# CHARGE.net
KiCad netlist of a schematic drawn in EAGLE
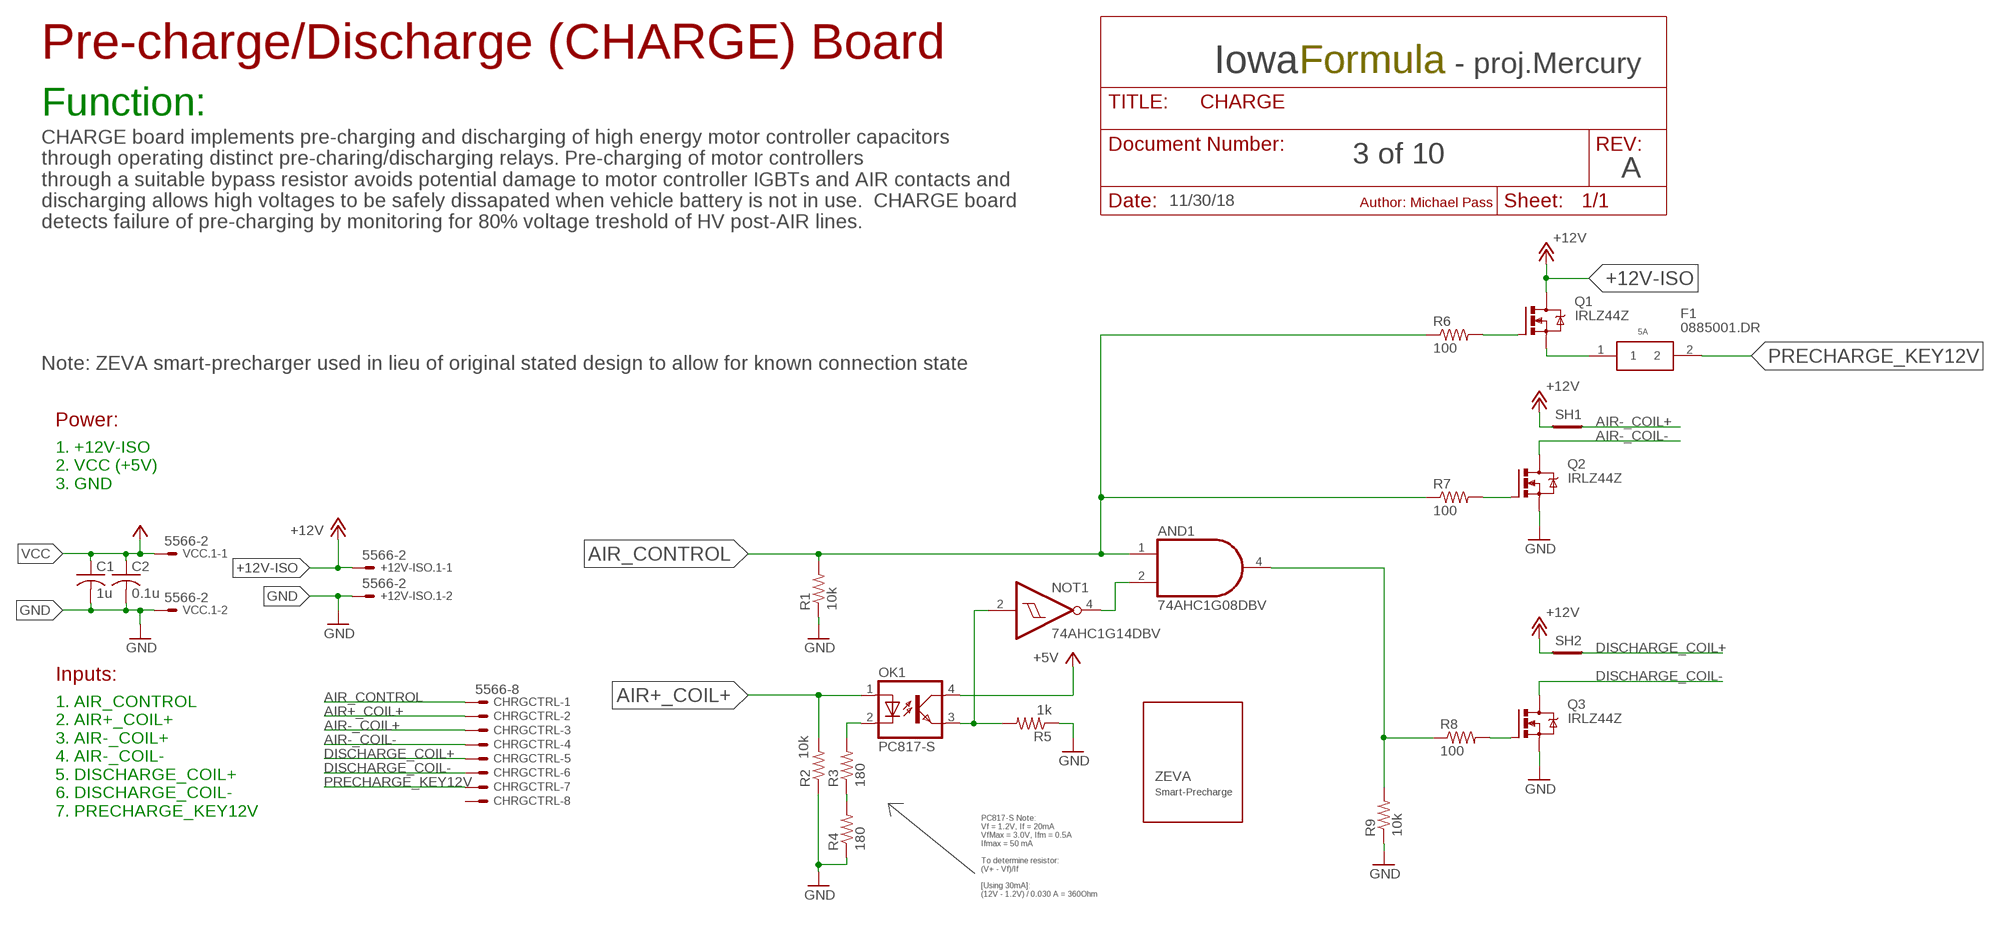
[diagram p0: schematic, sheet 1]

(export (version "E")
  (design (tool "Eeschema 10.0.6"))
  (components
    (comp (ref "+12V-ISO.1")
      (value "5566-2")
      (footprint "eagle-import:5566-2")
      (fields (field (name "MF") "MOLEX"))
      (libsource (lib "eagle-import") (part "5566-2"))
    )
    (comp (ref "AND1")
      (value "74AHC1G08DBV")
      (footprint "eagle-import:SOT23-5")
      (libsource (lib "eagle-import") (part "741G08DBVAHC"))
    )
    (comp (ref "C1")
      (value "1u")
      (footprint "eagle-import:C0805")
      (libsource (lib "eagle-import") (part "C-USC0805"))
    )
    (comp (ref "C2")
      (value "0.1u")
      (footprint "eagle-import:C0805")
      (libsource (lib "eagle-import") (part "C-USC0805"))
    )
    (comp (ref "CHRGCTRL")
      (value "5566-8")
      (footprint "eagle-import:5566-8")
      (fields (field (name "MF") "MOLEX"))
      (libsource (lib "eagle-import") (part "5566-8"))
    )
    (comp (ref "F1")
      (value "0885001.DR")
      (footprint "eagle-import:FUSC10948X488N")
      (fields (field (name "MOUSER_PART_NUMBER") "576-0885001.DR"))
      (libsource (lib "eagle-import") (part "0885001.DR"))
    )
    (comp (ref "NOT1")
      (value "74AHC1G14DBV")
      (footprint "eagle-import:SOT23-5")
      (libsource (lib "eagle-import") (part "741G14DBVAHC"))
    )
    (comp (ref "OK1")
      (value "PC817-S")
      (footprint "eagle-import:SOP04(2.54)")
      (libsource (lib "eagle-import") (part "PC817-S"))
    )
    (comp (ref "Q1")
      (value "IRLZ44Z")
      (footprint "eagle-import:TO220BH")
      (libsource (lib "eagle-import") (part "IRLZ44Z"))
    )
    (comp (ref "Q2")
      (value "IRLZ44Z")
      (footprint "eagle-import:TO220BH")
      (libsource (lib "eagle-import") (part "IRLZ44Z"))
    )
    (comp (ref "Q3")
      (value "IRLZ44Z")
      (footprint "eagle-import:TO220BH")
      (libsource (lib "eagle-import") (part "IRLZ44Z"))
    )
    (comp (ref "R1")
      (value "10k")
      (footprint "eagle-import:R0805")
      (libsource (lib "eagle-import") (part "R-US_R0805"))
    )
    (comp (ref "R2")
      (value "10k")
      (footprint "eagle-import:R0805")
      (libsource (lib "eagle-import") (part "R-US_R0805"))
    )
    (comp (ref "R3")
      (value "180")
      (footprint "eagle-import:R0805")
      (libsource (lib "eagle-import") (part "R-US_R0805"))
    )
    (comp (ref "R4")
      (value "180")
      (footprint "eagle-import:R0805")
      (libsource (lib "eagle-import") (part "R-US_R0805"))
    )
    (comp (ref "R5")
      (value "1k")
      (footprint "eagle-import:R0805")
      (libsource (lib "eagle-import") (part "R-US_R0805"))
    )
    (comp (ref "R6")
      (value "100")
      (footprint "eagle-import:R0805")
      (libsource (lib "eagle-import") (part "R-US_R0805"))
    )
    (comp (ref "R7")
      (value "100")
      (footprint "eagle-import:R0805")
      (libsource (lib "eagle-import") (part "R-US_R0805"))
    )
    (comp (ref "R8")
      (value "100")
      (footprint "eagle-import:R0805")
      (libsource (lib "eagle-import") (part "R-US_R0805"))
    )
    (comp (ref "R9")
      (value "10k")
      (footprint "eagle-import:R0805")
      (libsource (lib "eagle-import") (part "R-US_R0805"))
    )
    (comp (ref "SH1")
      (value "SHORTA5")
      (footprint "eagle-import:SHORT_ALL-50")
      (libsource (lib "eagle-import") (part "SHORTA5"))
    )
    (comp (ref "SH2")
      (value "SHORTA5")
      (footprint "eagle-import:SHORT_ALL-50")
      (libsource (lib "eagle-import") (part "SHORTA5"))
    )
    (comp (ref "U$1")
      (value "ZEVA_SMART-PRECHARGE")
      (footprint "eagle-import:ZEVA")
      (libsource (lib "eagle-import") (part "ZEVA_SMART-PRECHARGE"))
    )
    (comp (ref "VCC.1")
      (value "5566-2")
      (footprint "eagle-import:5566-2")
      (fields (field (name "MF") "MOLEX"))
      (libsource (lib "eagle-import") (part "5566-2"))
    )
  )
  (nets
    (net (code "1") (name "+12V-ISO") (class "Default")
      (node (ref "+12V-ISO.1") (pin "1") (pinfunction "S_1") (pintype "passive"))
      (node (ref "Q1") (pin "D") (pinfunction "D_D") (pintype "passive"))
      (node (ref "SH1") (pin "1") (pinfunction "P$1_1") (pintype "bidirectional"))
      (node (ref "SH2") (pin "1") (pinfunction "P$1_1") (pintype "bidirectional"))
    )
    (net (code "2") (name "/AIR-_COIL+") (class "Default")
      (node (ref "CHRGCTRL") (pin "3") (pinfunction "S_3") (pintype "passive"))
      (node (ref "SH1") (pin "2") (pinfunction "P$2_2") (pintype "bidirectional"))
    )
    (net (code "3") (name "/AIR-_COIL-") (class "Default")
      (node (ref "CHRGCTRL") (pin "4") (pinfunction "S_4") (pintype "passive"))
      (node (ref "Q2") (pin "D") (pinfunction "D_D") (pintype "passive"))
    )
    (net (code "4") (name "/DISCHARGE_COIL+") (class "Default")
      (node (ref "CHRGCTRL") (pin "5") (pinfunction "S_5") (pintype "passive"))
      (node (ref "SH2") (pin "2") (pinfunction "P$2_2") (pintype "bidirectional"))
    )
    (net (code "5") (name "/DISCHARGE_COIL-") (class "Default")
      (node (ref "CHRGCTRL") (pin "6") (pinfunction "S_6") (pintype "passive"))
      (node (ref "Q3") (pin "D") (pinfunction "D_D") (pintype "passive"))
    )
    (net (code "6") (name "AIR+_COIL+") (class "Default")
      (node (ref "CHRGCTRL") (pin "2") (pinfunction "S_2") (pintype "passive"))
      (node (ref "OK1") (pin "1") (pinfunction "A_1") (pintype "passive"))
      (node (ref "R2") (pin "2") (pinfunction "2_2") (pintype "passive"))
    )
    (net (code "7") (name "AIR_CONTROL") (class "Default")
      (node (ref "AND1") (pin "1") (pinfunction "I0_1") (pintype "input"))
      (node (ref "CHRGCTRL") (pin "1") (pinfunction "S_1") (pintype "passive"))
      (node (ref "R1") (pin "2") (pinfunction "2_2") (pintype "passive"))
      (node (ref "R6") (pin "1") (pinfunction "1_1") (pintype "passive"))
      (node (ref "R7") (pin "1") (pinfunction "1_1") (pintype "passive"))
    )
    (net (code "8") (name "GND") (class "Default")
      (node (ref "+12V-ISO.1") (pin "2") (pinfunction "S_2") (pintype "passive"))
      (node (ref "C1") (pin "2") (pinfunction "2_2") (pintype "passive"))
      (node (ref "C2") (pin "2") (pinfunction "2_2") (pintype "passive"))
      (node (ref "Q2") (pin "S") (pinfunction "S_S") (pintype "passive"))
      (node (ref "Q3") (pin "S") (pinfunction "S_S") (pintype "passive"))
      (node (ref "R1") (pin "1") (pinfunction "1_1") (pintype "passive"))
      (node (ref "R2") (pin "1") (pinfunction "1_1") (pintype "passive"))
      (node (ref "R4") (pin "1") (pinfunction "1_1") (pintype "passive"))
      (node (ref "R5") (pin "1") (pinfunction "1_1") (pintype "passive"))
      (node (ref "R9") (pin "1") (pinfunction "1_1") (pintype "passive"))
      (node (ref "VCC.1") (pin "2") (pinfunction "S_2") (pintype "passive"))
    )
    (net (code "9") (name "Net-(AND1A-I1)") (class "Default")
      (node (ref "AND1") (pin "2") (pinfunction "I1_2") (pintype "input"))
      (node (ref "NOT1") (pin "4") (pinfunction "O_4") (pintype "output"))
    )
    (net (code "10") (name "Net-(AND1A-O)") (class "Default")
      (node (ref "AND1") (pin "4") (pinfunction "O_4") (pintype "output"))
      (node (ref "R8") (pin "1") (pinfunction "1_1") (pintype "passive"))
      (node (ref "R9") (pin "2") (pinfunction "2_2") (pintype "passive"))
    )
    (net (code "11") (name "Net-(F1-Pad1)") (class "Default")
      (node (ref "F1") (pin "1") (pinfunction "1_1") (pintype "bidirectional"))
      (node (ref "Q1") (pin "S") (pinfunction "S_S") (pintype "passive"))
    )
    (net (code "12") (name "Net-(NOT1A-I)") (class "Default")
      (node (ref "NOT1") (pin "2") (pinfunction "I_2") (pintype "input"))
      (node (ref "OK1") (pin "3") (pinfunction "EMIT_3") (pintype "passive"))
      (node (ref "R5") (pin "2") (pinfunction "2_2") (pintype "passive"))
    )
    (net (code "13") (name "Net-(OK1-C)") (class "Default")
      (node (ref "OK1") (pin "2") (pinfunction "C_2") (pintype "passive"))
      (node (ref "R3") (pin "2") (pinfunction "2_2") (pintype "passive"))
    )
    (net (code "14") (name "Net-(Q1-PadG)") (class "Default")
      (node (ref "Q1") (pin "G") (pinfunction "G_G") (pintype "passive"))
      (node (ref "R6") (pin "2") (pinfunction "2_2") (pintype "passive"))
    )
    (net (code "15") (name "Net-(Q2-PadG)") (class "Default")
      (node (ref "Q2") (pin "G") (pinfunction "G_G") (pintype "passive"))
      (node (ref "R7") (pin "2") (pinfunction "2_2") (pintype "passive"))
    )
    (net (code "16") (name "Net-(Q3-PadG)") (class "Default")
      (node (ref "Q3") (pin "G") (pinfunction "G_G") (pintype "passive"))
      (node (ref "R8") (pin "2") (pinfunction "2_2") (pintype "passive"))
    )
    (net (code "17") (name "Net-(R3-Pad1)") (class "Default")
      (node (ref "R3") (pin "1") (pinfunction "1_1") (pintype "passive"))
      (node (ref "R4") (pin "2") (pinfunction "2_2") (pintype "passive"))
    )
    (net (code "18") (name "PRECHARGE_KEY12V") (class "Default")
      (node (ref "CHRGCTRL") (pin "7") (pinfunction "S_7") (pintype "passive"))
      (node (ref "F1") (pin "2") (pinfunction "2_2") (pintype "bidirectional"))
    )
    (net (code "19") (name "VCC") (class "Default")
      (node (ref "C1") (pin "1") (pinfunction "1_1") (pintype "passive"))
      (node (ref "C2") (pin "1") (pinfunction "1_1") (pintype "passive"))
      (node (ref "OK1") (pin "4") (pinfunction "COL_4") (pintype "passive"))
      (node (ref "VCC.1") (pin "1") (pinfunction "S_1") (pintype "passive"))
    )
    (net (code "20") (name "unconnected-(CHRGCTRLH-S-Pad8)") (class "Default")
      (node (ref "CHRGCTRL") (pin "8") (pinfunction "S_8") (pintype "passive"))
    )
  )
)
